# Thermistor.net
KiCad netlist of a schematic drawn in Altium Designer
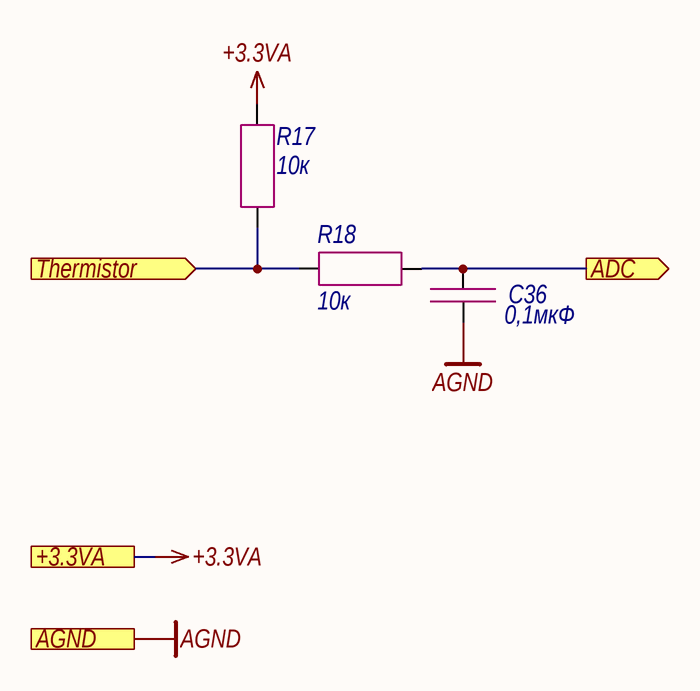
[diagram p0: Thermistor.SchDoc]

(export (version "E")
  (design (tool "Eeschema 10.0.6"))
  (components
    (comp (ref "C36")
      (value "0,1мкФ")
      (footprint "Pcb_library:CAP_0603")
      (fields (field (name "MANUFACTURER") "Murata"))
      (libsource (lib "Schem_library") (part "Capacitor"))
    )
    (comp (ref "R17")
      (value "10к")
      (footprint "Pcb_library:RES_0603")
      (fields (field (name "MANUFACTURER") "Yageo"))
      (libsource (lib "Schem_library") (part "Resistor"))
    )
    (comp (ref "R18")
      (value "10к")
      (footprint "Pcb_library:RES_0603")
      (fields (field (name "MANUFACTURER") "Yageo"))
      (libsource (lib "Schem_library") (part "Resistor"))
    )
  )
  (nets
    (net (code "1") (name "+3.3VA") (class "Default")
      (node (ref "R17") (pin "1") (pinfunction "1_1") (pintype "passive"))
    )
    (net (code "2") (name "/ADC") (class "Default")
      (node (ref "C36") (pin "1") (pinfunction "1_1") (pintype "passive"))
      (node (ref "R18") (pin "2") (pinfunction "2_2") (pintype "passive"))
    )
    (net (code "3") (name "/Thermistor") (class "Default")
      (node (ref "R17") (pin "2") (pinfunction "2_2") (pintype "passive"))
      (node (ref "R18") (pin "1") (pinfunction "1_1") (pintype "passive"))
    )
    (net (code "4") (name "AGND") (class "Default")
      (node (ref "C36") (pin "2") (pinfunction "2_2") (pintype "passive"))
    )
  )
)
